# 10_SPI_schdoc.net
KiCad netlist of a schematic drawn in Altium Designer
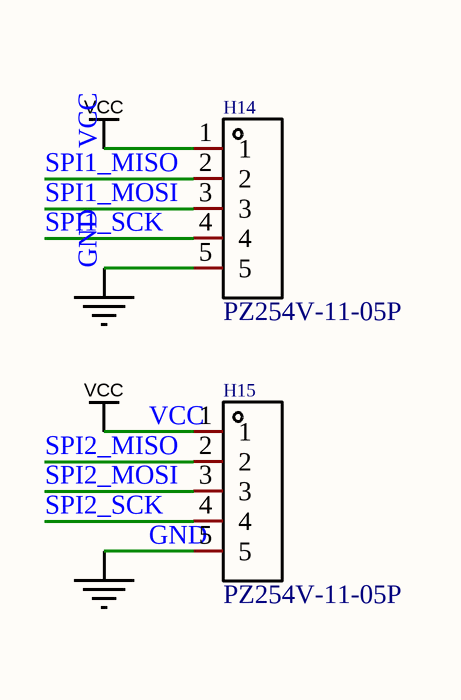
[diagram p0: 10_SPI.schdoc.schdoc]

(export (version "E")
  (design (tool "Eeschema 10.0.6"))
  (components
    (comp (ref "H14")
      (value "PZ254V-11-05P")
      (fields (field (name "NAME") "PZ254V-11-05P") (field (name "MANUFACTURER") "XFCN(兴飞)"))
      (libsource (lib "altium-import") (part "root_0_PZ254V-11-05P_"))
    )
    (comp (ref "H15")
      (value "PZ254V-11-05P")
      (fields (field (name "NAME") "PZ254V-11-05P") (field (name "MANUFACTURER") "XFCN(兴飞)"))
      (libsource (lib "altium-import") (part "root_0_PZ254V-11-05P_"))
    )
  )
  (nets
    (net (code "1") (name "/GND") (class "Default")
      (node (ref "H14") (pin "5") (pinfunction "5_5") (pintype "passive"))
      (node (ref "H15") (pin "5") (pinfunction "5_5") (pintype "passive"))
    )
    (net (code "2") (name "/SPI1_MISO") (class "Default")
      (node (ref "H14") (pin "2") (pinfunction "2_2") (pintype "passive"))
    )
    (net (code "3") (name "/SPI1_MOSI") (class "Default")
      (node (ref "H14") (pin "3") (pinfunction "3_3") (pintype "passive"))
    )
    (net (code "4") (name "/SPI1_SCK") (class "Default")
      (node (ref "H14") (pin "4") (pinfunction "4_4") (pintype "passive"))
    )
    (net (code "5") (name "/SPI2_MISO") (class "Default")
      (node (ref "H15") (pin "2") (pinfunction "2_2") (pintype "passive"))
    )
    (net (code "6") (name "/SPI2_MOSI") (class "Default")
      (node (ref "H15") (pin "3") (pinfunction "3_3") (pintype "passive"))
    )
    (net (code "7") (name "/SPI2_SCK") (class "Default")
      (node (ref "H15") (pin "4") (pinfunction "4_4") (pintype "passive"))
    )
    (net (code "8") (name "VCC") (class "Default")
      (node (ref "H14") (pin "1") (pinfunction "1_1") (pintype "passive"))
      (node (ref "H15") (pin "1") (pinfunction "1_1") (pintype "passive"))
    )
  )
)
